# as14120_x31_adc.net
KiCad netlist of a schematic drawn in Altium Designer
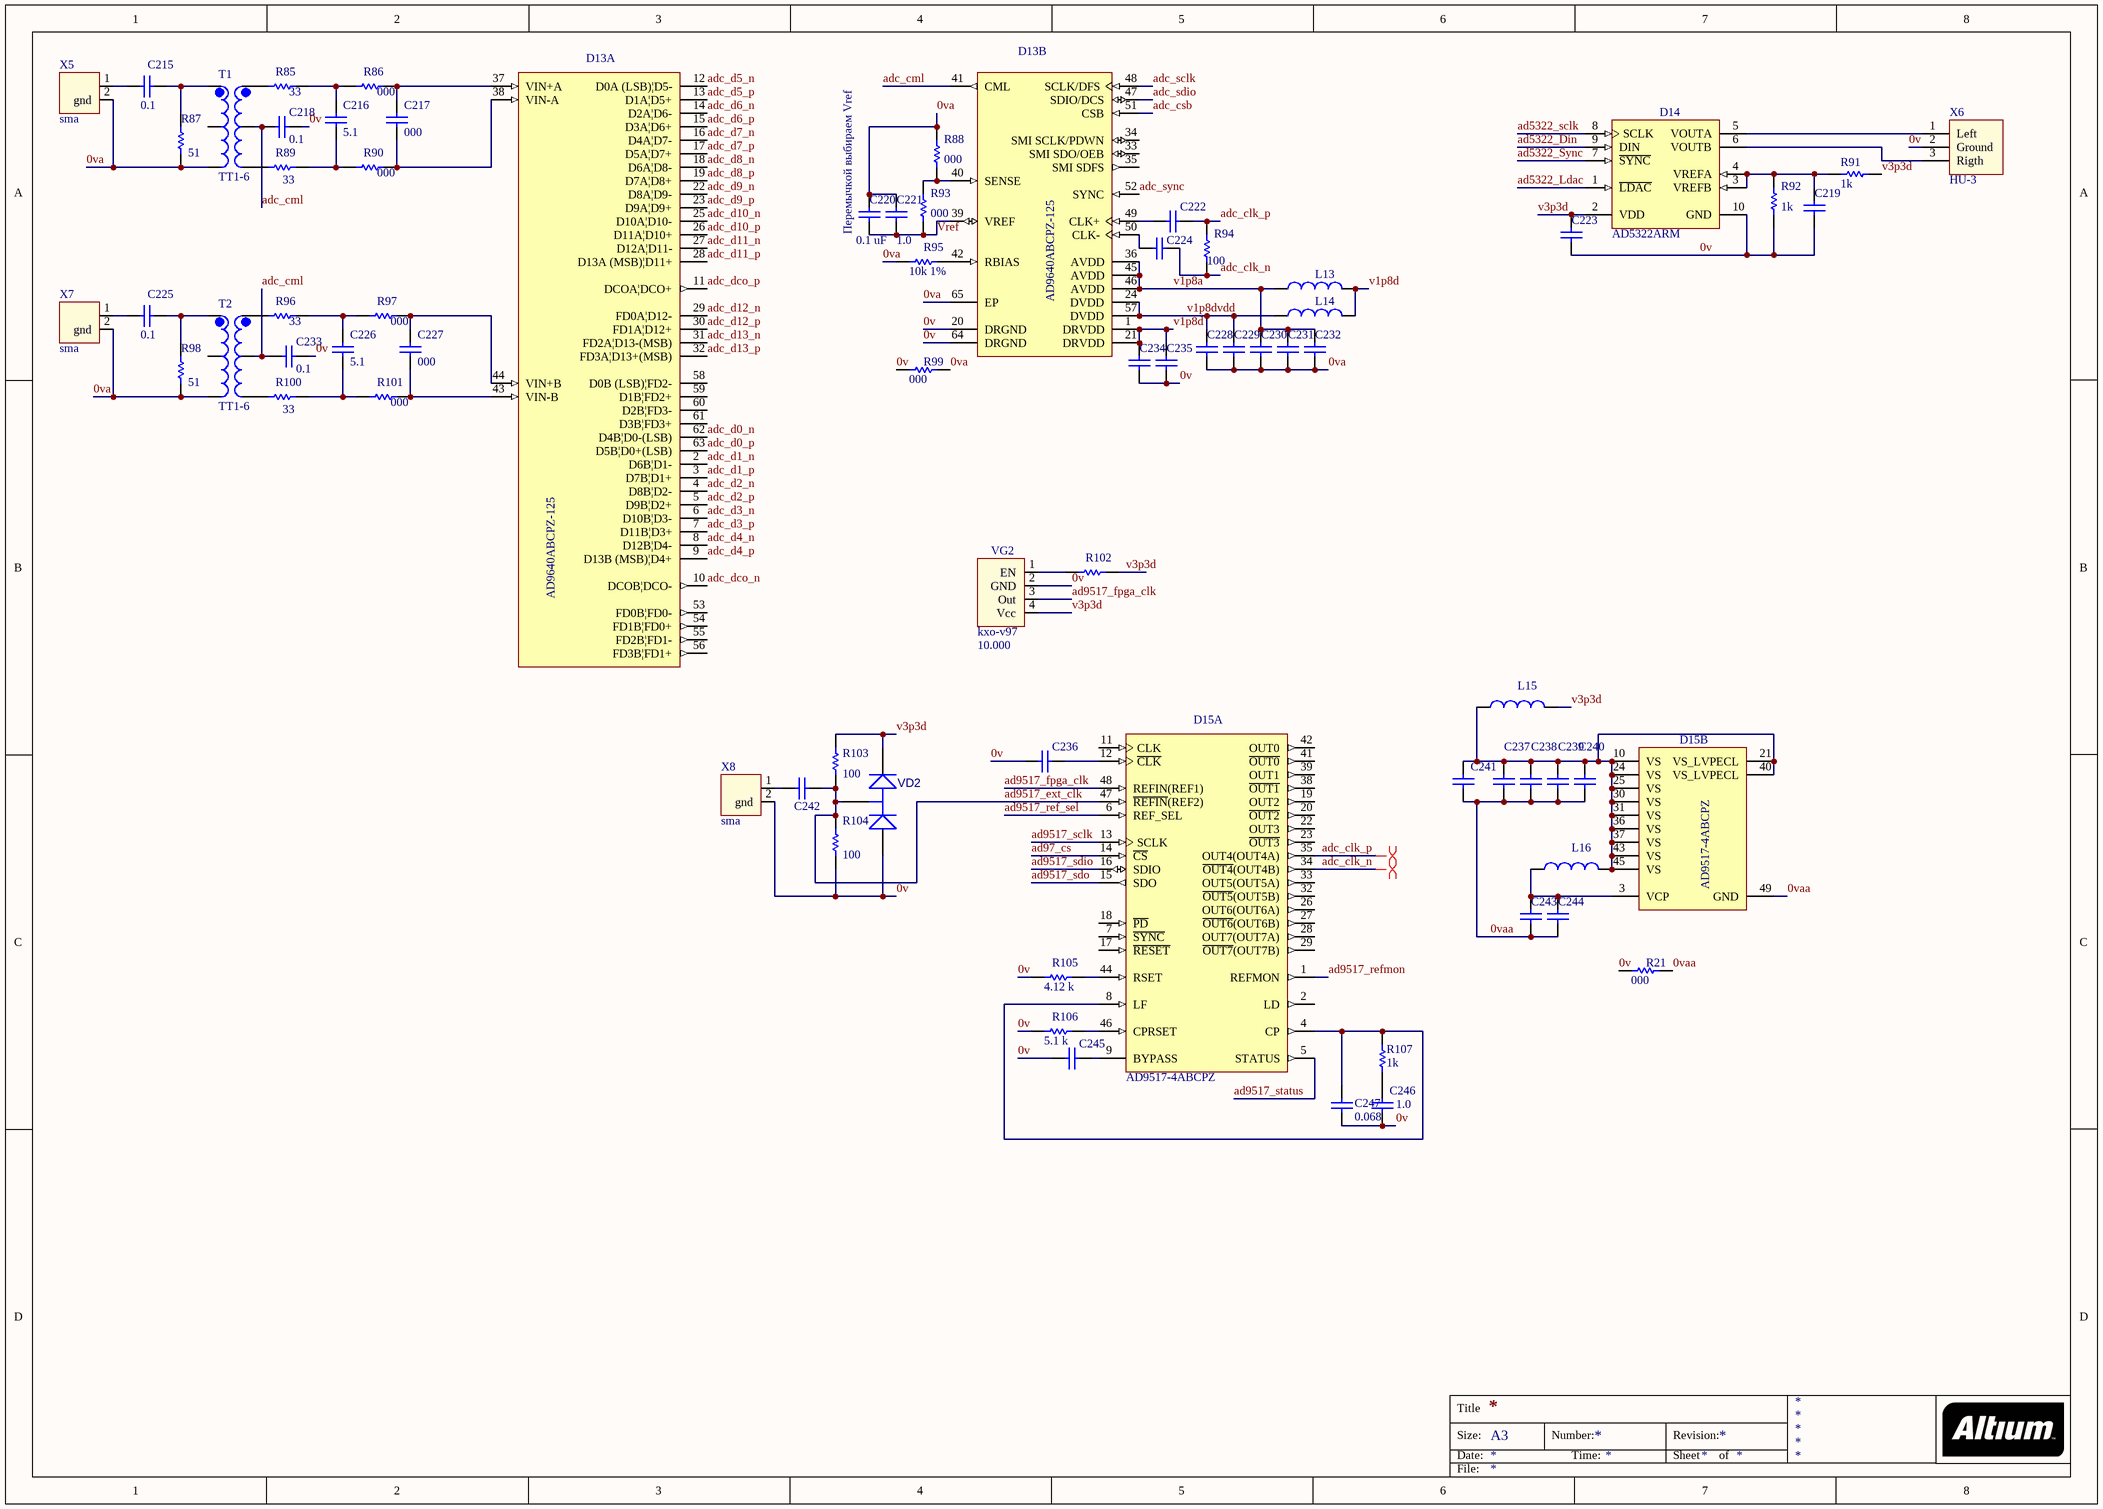
[diagram p0: as14120_x31_adc.SchDoc]

(export (version "E")
  (design (tool "Eeschema 10.0.6"))
  (components
    (comp (ref "C215")
      (value "0.1")
      (footprint "CAPC0402(1005)60_M")
      (description "CAP 1uF 10V ±20% 0402 (1005 Metric) Thickness 0.6mm SMD")
      (fields (field (name "TOLERANCE") "±20%") (field (name "Comment") "CAP 1uF 10V 0402(1005)"))
      (libsource (lib "as14120") (part "CAP_0402"))
    )
    (comp (ref "C216")
      (value "5.1")
      (footprint "CAPC0805(2012)100_N")
      (fields (field (name "Comment") "CAP_0805"))
      (libsource (lib "as14120") (part "CAP_0805"))
    )
    (comp (ref "C217")
      (value "000")
      (footprint "CAPC0805(2012)100_N")
      (fields (field (name "Comment") "CAP_0805"))
      (libsource (lib "as14120") (part "CAP_0805"))
    )
    (comp (ref "C218")
      (value "0.1")
      (footprint "CAPC0402(1005)60_M")
      (description "CAP 1uF 10V ±20% 0402 (1005 Metric) Thickness 0.6mm SMD")
      (fields (field (name "TOLERANCE") "±20%") (field (name "Comment") "CAP 1uF 10V 0402(1005)"))
      (libsource (lib "as14120") (part "CAP_0402"))
    )
    (comp (ref "C219")
      (value "CAP 1uF 10V 0402(1005)")
      (footprint "CAPC0402(1005)60_M")
      (description "CAP 1uF 10V ±20% 0402 (1005 Metric) Thickness 0.6mm SMD")
      (fields (field (name "TOLERANCE") "±20%"))
      (libsource (lib "as14120") (part "CAP_0402"))
    )
    (comp (ref "C220")
      (value "0.1 uF")
      (footprint "CAPC0402(1005)60_M")
      (description "CAP 1uF 10V ±20% 0402 (1005 Metric) Thickness 0.6mm SMD")
      (fields (field (name "TOLERANCE") "±20%") (field (name "Comment") "CAP 1uF 10V 0402(1005)"))
      (libsource (lib "as14120") (part "CAP_0402"))
    )
    (comp (ref "C221")
      (value "1.0")
      (footprint "CAPC0402(1005)60_M")
      (description "CAP 1uF 10V ±20% 0402 (1005 Metric) Thickness 0.6mm SMD")
      (fields (field (name "TOLERANCE") "±20%") (field (name "Comment") "CAP 1uF 10V 0402(1005)"))
      (libsource (lib "as14120") (part "CAP_0402"))
    )
    (comp (ref "C222")
      (value "CAP 1uF 10V 0402(1005)")
      (footprint "CAPC0402(1005)60_M")
      (description "CAP 1uF 10V ±20% 0402 (1005 Metric) Thickness 0.6mm SMD")
      (fields (field (name "TOLERANCE") "±20%"))
      (libsource (lib "as14120") (part "CAP_0402"))
    )
    (comp (ref "C223")
      (value "CAP 1uF 10V 0402(1005)")
      (footprint "CAPC0402(1005)60_M")
      (description "CAP 1uF 10V ±20% 0402 (1005 Metric) Thickness 0.6mm SMD")
      (fields (field (name "TOLERANCE") "±20%"))
      (libsource (lib "as14120") (part "CAP_0402"))
    )
    (comp (ref "C224")
      (value "CAP 1uF 10V 0402(1005)")
      (footprint "CAPC0402(1005)60_M")
      (description "CAP 1uF 10V ±20% 0402 (1005 Metric) Thickness 0.6mm SMD")
      (fields (field (name "TOLERANCE") "±20%"))
      (libsource (lib "as14120") (part "CAP_0402"))
    )
    (comp (ref "C225")
      (value "0.1")
      (footprint "CAPC0402(1005)60_M")
      (description "CAP 1uF 10V ±20% 0402 (1005 Metric) Thickness 0.6mm SMD")
      (fields (field (name "TOLERANCE") "±20%") (field (name "Comment") "CAP 1uF 10V 0402(1005)"))
      (libsource (lib "as14120") (part "CAP_0402"))
    )
    (comp (ref "C226")
      (value "5.1")
      (footprint "CAPC0805(2012)100_N")
      (fields (field (name "Comment") "CAP_0805"))
      (libsource (lib "as14120") (part "CAP_0805"))
    )
    (comp (ref "C227")
      (value "000")
      (footprint "CAPC0805(2012)100_N")
      (fields (field (name "Comment") "CAP_0805"))
      (libsource (lib "as14120") (part "CAP_0805"))
    )
    (comp (ref "C228")
      (value "CAP 1uF 10V 0402(1005)")
      (footprint "CAPC0402(1005)60_M")
      (description "CAP 1uF 10V ±20% 0402 (1005 Metric) Thickness 0.6mm SMD")
      (fields (field (name "TOLERANCE") "±20%"))
      (libsource (lib "as14120") (part "CAP_0402"))
    )
    (comp (ref "C229")
      (value "CAP 1uF 10V 0402(1005)")
      (footprint "CAPC0402(1005)60_M")
      (description "CAP 1uF 10V ±20% 0402 (1005 Metric) Thickness 0.6mm SMD")
      (fields (field (name "TOLERANCE") "±20%"))
      (libsource (lib "as14120") (part "CAP_0402"))
    )
    (comp (ref "C230")
      (value "CAP 1uF 10V 0402(1005)")
      (footprint "CAPC0402(1005)60_M")
      (description "CAP 1uF 10V ±20% 0402 (1005 Metric) Thickness 0.6mm SMD")
      (fields (field (name "TOLERANCE") "±20%"))
      (libsource (lib "as14120") (part "CAP_0402"))
    )
    (comp (ref "C231")
      (value "CAP 1uF 10V 0402(1005)")
      (footprint "CAPC0402(1005)60_M")
      (description "CAP 1uF 10V ±20% 0402 (1005 Metric) Thickness 0.6mm SMD")
      (fields (field (name "TOLERANCE") "±20%"))
      (libsource (lib "as14120") (part "CAP_0402"))
    )
    (comp (ref "C232")
      (value "CAP 1uF 10V 0402(1005)")
      (footprint "CAPC0402(1005)60_M")
      (description "CAP 1uF 10V ±20% 0402 (1005 Metric) Thickness 0.6mm SMD")
      (fields (field (name "TOLERANCE") "±20%"))
      (libsource (lib "as14120") (part "CAP_0402"))
    )
    (comp (ref "C233")
      (value "0.1")
      (footprint "CAPC0402(1005)60_M")
      (description "CAP 1uF 10V ±20% 0402 (1005 Metric) Thickness 0.6mm SMD")
      (fields (field (name "TOLERANCE") "±20%") (field (name "Comment") "CAP 1uF 10V 0402(1005)"))
      (libsource (lib "as14120") (part "CAP_0402"))
    )
    (comp (ref "C234")
      (value "CAP 1uF 10V 0402(1005)")
      (footprint "CAPC0402(1005)60_M")
      (description "CAP 1uF 10V ±20% 0402 (1005 Metric) Thickness 0.6mm SMD")
      (fields (field (name "TOLERANCE") "±20%"))
      (libsource (lib "as14120") (part "CAP_0402"))
    )
    (comp (ref "C235")
      (value "CAP 1uF 10V 0402(1005)")
      (footprint "CAPC0402(1005)60_M")
      (description "CAP 1uF 10V ±20% 0402 (1005 Metric) Thickness 0.6mm SMD")
      (fields (field (name "TOLERANCE") "±20%"))
      (libsource (lib "as14120") (part "CAP_0402"))
    )
    (comp (ref "C236")
      (value "CAP 1uF 10V 0402(1005)")
      (footprint "CAPC0402(1005)60_M")
      (description "CAP 1uF 10V ±20% 0402 (1005 Metric) Thickness 0.6mm SMD")
      (fields (field (name "TOLERANCE") "±20%"))
      (libsource (lib "as14120") (part "CAP_0402"))
    )
    (comp (ref "C237")
      (value "CAP 1uF 10V 0402(1005)")
      (footprint "CAPC0402(1005)60_M")
      (description "CAP 1uF 10V ±20% 0402 (1005 Metric) Thickness 0.6mm SMD")
      (fields (field (name "TOLERANCE") "±20%"))
      (libsource (lib "as14120") (part "CAP_0402"))
    )
    (comp (ref "C238")
      (value "CAP 1uF 10V 0402(1005)")
      (footprint "CAPC0402(1005)60_M")
      (description "CAP 1uF 10V ±20% 0402 (1005 Metric) Thickness 0.6mm SMD")
      (fields (field (name "TOLERANCE") "±20%"))
      (libsource (lib "as14120") (part "CAP_0402"))
    )
    (comp (ref "C239")
      (value "CAP 1uF 10V 0402(1005)")
      (footprint "CAPC0402(1005)60_M")
      (description "CAP 1uF 10V ±20% 0402 (1005 Metric) Thickness 0.6mm SMD")
      (fields (field (name "TOLERANCE") "±20%"))
      (libsource (lib "as14120") (part "CAP_0402"))
    )
    (comp (ref "C240")
      (value "CAP 1uF 10V 0402(1005)")
      (footprint "CAPC0402(1005)60_M")
      (description "CAP 1uF 10V ±20% 0402 (1005 Metric) Thickness 0.6mm SMD")
      (fields (field (name "TOLERANCE") "±20%"))
      (libsource (lib "as14120") (part "CAP_0402"))
    )
    (comp (ref "C241")
      (value "CAP 1uF 10V 0402(1005)")
      (footprint "CAPC0402(1005)60_M")
      (description "CAP 1uF 10V ±20% 0402 (1005 Metric) Thickness 0.6mm SMD")
      (fields (field (name "TOLERANCE") "±20%"))
      (libsource (lib "as14120") (part "CAP_0402"))
    )
    (comp (ref "C242")
      (value "CAP 1uF 10V 0402(1005)")
      (footprint "CAPC0402(1005)60_M")
      (description "CAP 1uF 10V ±20% 0402 (1005 Metric) Thickness 0.6mm SMD")
      (fields (field (name "TOLERANCE") "±20%"))
      (libsource (lib "as14120") (part "CAP_0402"))
    )
    (comp (ref "C243")
      (value "CAP 1uF 10V 0402(1005)")
      (footprint "CAPC0402(1005)60_M")
      (description "CAP 1uF 10V ±20% 0402 (1005 Metric) Thickness 0.6mm SMD")
      (fields (field (name "TOLERANCE") "±20%"))
      (libsource (lib "as14120") (part "CAP_0402"))
    )
    (comp (ref "C244")
      (value "CAP 1uF 10V 0402(1005)")
      (footprint "CAPC0402(1005)60_M")
      (description "CAP 1uF 10V ±20% 0402 (1005 Metric) Thickness 0.6mm SMD")
      (fields (field (name "TOLERANCE") "±20%"))
      (libsource (lib "as14120") (part "CAP_0402"))
    )
    (comp (ref "C245")
      (value "CAP 1uF 10V 0402(1005)")
      (footprint "CAPC0402(1005)60_M")
      (description "CAP 1uF 10V ±20% 0402 (1005 Metric) Thickness 0.6mm SMD")
      (fields (field (name "TOLERANCE") "±20%"))
      (libsource (lib "as14120") (part "CAP_0402"))
    )
    (comp (ref "C246")
      (value "1.0")
      (footprint "CAPC0805(2012)100_N")
      (fields (field (name "Comment") "CAP_0805"))
      (libsource (lib "as14120") (part "CAP_0805"))
    )
    (comp (ref "C247")
      (value "0.068")
      (footprint "CAPC0805(2012)100_N")
      (fields (field (name "Comment") "CAP_0805"))
      (libsource (lib "as14120") (part "CAP_0805"))
    )
    (comp (ref "D13")
      (value "AD9640ABCPZ-125")
      (footprint "CP-64-6_N")
      (fields (field (name "PART NUMBER") "AD9640-125") (field (name "MANUFACTURER") "Analog Devices"))
      (libsource (lib "Analog Devices Data Converters Analog-to-Digital Converters") (part "AD9640ABCPZ-125"))
    )
    (comp (ref "D14")
      (value "AD5322ARM")
      (footprint "RM-10_L")
      (fields (field (name "ADI PART NUMBER") "AD5322") (field (name "MANUFACTURER") "Analog Devices"))
      (libsource (lib "Analog Devices Data Converters Digital-to-Analog Converters") (part "AD5322ARM"))
    )
    (comp (ref "D15")
      (value "AD9517-4ABCPZ")
      (footprint "ADI-CP-48-8_L")
      (libsource (lib "Analog Devices RF IF Timing ICs and Clocks") (part "AD9517-4ABCPZ"))
    )
    (comp (ref "L13")
      (value "BLM21PG300SN1D")
      (footprint "CAPC0805(2012)100_N")
      (libsource (lib "as14120") (part "Ferrite_beat"))
    )
    (comp (ref "L14")
      (value "BLM21PG300SN1D")
      (footprint "CAPC0805(2012)100_N")
      (libsource (lib "as14120") (part "Ferrite_beat"))
    )
    (comp (ref "L15")
      (value "BLM21PG300SN1D")
      (footprint "CAPC0805(2012)100_N")
      (libsource (lib "as14120") (part "Ferrite_beat"))
    )
    (comp (ref "L16")
      (value "BLM21PG300SN1D")
      (footprint "CAPC0805(2012)100_N")
      (libsource (lib "as14120") (part "Ferrite_beat"))
    )
    (comp (ref "R21")
      (value "000")
      (footprint "RESC0603(1608)_L")
      (description "1K 0.1W 5% 0603 (1608 Metric)  SMD")
      (fields (field (name "TOLERANCE") "5 %") (field (name "POWER") "0.1 W"))
      (libsource (lib "as14120") (part "RES_0603"))
    )
    (comp (ref "R85")
      (value "33")
      (footprint "RESC0805(2012)_L")
      (description "1K 0.125W 1% 0805 (2012 Metric)  SMD")
      (fields (field (name "TOLERANCE") "1 %") (field (name "POWER") "0.125 W"))
      (libsource (lib "as14120") (part "RES_0805"))
    )
    (comp (ref "R86")
      (value "000")
      (footprint "RESC0805(2012)_L")
      (description "1K 0.125W 1% 0805 (2012 Metric)  SMD")
      (fields (field (name "TOLERANCE") "1 %") (field (name "POWER") "0.125 W"))
      (libsource (lib "as14120") (part "RES_0805"))
    )
    (comp (ref "R87")
      (value "51")
      (footprint "RESC0805(2012)_L")
      (description "1K 0.125W 1% 0805 (2012 Metric)  SMD")
      (fields (field (name "TOLERANCE") "1 %") (field (name "POWER") "0.125 W"))
      (libsource (lib "as14120") (part "RES_0805"))
    )
    (comp (ref "R88")
      (value "000")
      (footprint "RESC0603(1608)_L")
      (description "1K 0.1W 5% 0603 (1608 Metric)  SMD")
      (fields (field (name "TOLERANCE") "5 %") (field (name "POWER") "0.1 W"))
      (libsource (lib "as14120") (part "RES_0603"))
    )
    (comp (ref "R89")
      (value "33")
      (footprint "RESC0805(2012)_L")
      (description "1K 0.125W 1% 0805 (2012 Metric)  SMD")
      (fields (field (name "TOLERANCE") "1 %") (field (name "POWER") "0.125 W"))
      (libsource (lib "as14120") (part "RES_0805"))
    )
    (comp (ref "R90")
      (value "000")
      (footprint "RESC0805(2012)_L")
      (description "1K 0.125W 1% 0805 (2012 Metric)  SMD")
      (fields (field (name "TOLERANCE") "1 %") (field (name "POWER") "0.125 W"))
      (libsource (lib "as14120") (part "RES_0805"))
    )
    (comp (ref "R91")
      (value "1k")
      (footprint "RESC0603(1608)_L")
      (description "1K 0.1W 5% 0603 (1608 Metric)  SMD")
      (fields (field (name "TOLERANCE") "5 %") (field (name "POWER") "0.1 W"))
      (libsource (lib "as14120") (part "RES_0603"))
    )
    (comp (ref "R92")
      (value "1k")
      (footprint "RESC0603(1608)_L")
      (description "1K 0.1W 5% 0603 (1608 Metric)  SMD")
      (fields (field (name "TOLERANCE") "5 %") (field (name "POWER") "0.1 W"))
      (libsource (lib "as14120") (part "RES_0603"))
    )
    (comp (ref "R93")
      (value "000")
      (footprint "RESC0603(1608)_L")
      (description "1K 0.1W 5% 0603 (1608 Metric)  SMD")
      (fields (field (name "TOLERANCE") "5 %") (field (name "POWER") "0.1 W"))
      (libsource (lib "as14120") (part "RES_0603"))
    )
    (comp (ref "R94")
      (value "100")
      (footprint "RESC0805(2012)_L")
      (description "1K 0.125W 1% 0805 (2012 Metric)  SMD")
      (fields (field (name "TOLERANCE") "1 %") (field (name "POWER") "0.125 W"))
      (libsource (lib "as14120") (part "RES_0805"))
    )
    (comp (ref "R95")
      (value "10k 1%")
      (footprint "RESC0805(2012)_L")
      (description "1K 0.125W 1% 0805 (2012 Metric)  SMD")
      (fields (field (name "TOLERANCE") "1 %") (field (name "POWER") "0.125 W"))
      (libsource (lib "as14120") (part "RES_0805"))
    )
    (comp (ref "R96")
      (value "33")
      (footprint "RESC0805(2012)_L")
      (description "1K 0.125W 1% 0805 (2012 Metric)  SMD")
      (fields (field (name "TOLERANCE") "1 %") (field (name "POWER") "0.125 W"))
      (libsource (lib "as14120") (part "RES_0805"))
    )
    (comp (ref "R97")
      (value "000")
      (footprint "RESC0805(2012)_L")
      (description "1K 0.125W 1% 0805 (2012 Metric)  SMD")
      (fields (field (name "TOLERANCE") "1 %") (field (name "POWER") "0.125 W"))
      (libsource (lib "as14120") (part "RES_0805"))
    )
    (comp (ref "R98")
      (value "51")
      (footprint "RESC0805(2012)_L")
      (description "1K 0.125W 1% 0805 (2012 Metric)  SMD")
      (fields (field (name "TOLERANCE") "1 %") (field (name "POWER") "0.125 W"))
      (libsource (lib "as14120") (part "RES_0805"))
    )
    (comp (ref "R99")
      (value "000")
      (footprint "RESC0603(1608)_L")
      (description "1K 0.1W 5% 0603 (1608 Metric)  SMD")
      (fields (field (name "TOLERANCE") "5 %") (field (name "POWER") "0.1 W"))
      (libsource (lib "as14120") (part "RES_0603"))
    )
    (comp (ref "R100")
      (value "33")
      (footprint "RESC0805(2012)_L")
      (description "1K 0.125W 1% 0805 (2012 Metric)  SMD")
      (fields (field (name "TOLERANCE") "1 %") (field (name "POWER") "0.125 W"))
      (libsource (lib "as14120") (part "RES_0805"))
    )
    (comp (ref "R101")
      (value "000")
      (footprint "RESC0805(2012)_L")
      (description "1K 0.125W 1% 0805 (2012 Metric)  SMD")
      (fields (field (name "TOLERANCE") "1 %") (field (name "POWER") "0.125 W"))
      (libsource (lib "as14120") (part "RES_0805"))
    )
    (comp (ref "R102")
      (value "1K 5% 0603(1608)")
      (footprint "RESC0603(1608)_L")
      (description "1K 0.1W 5% 0603 (1608 Metric)  SMD")
      (fields (field (name "TOLERANCE") "5 %") (field (name "POWER") "0.1 W"))
      (libsource (lib "as14120") (part "RES_0603"))
    )
    (comp (ref "R103")
      (value "100")
      (footprint "RESC0805(2012)_L")
      (description "1K 0.125W 1% 0805 (2012 Metric)  SMD")
      (fields (field (name "TOLERANCE") "1 %") (field (name "POWER") "0.125 W"))
      (libsource (lib "as14120") (part "RES_0805"))
    )
    (comp (ref "R104")
      (value "100")
      (footprint "RESC0805(2012)_L")
      (description "1K 0.125W 1% 0805 (2012 Metric)  SMD")
      (fields (field (name "TOLERANCE") "1 %") (field (name "POWER") "0.125 W"))
      (libsource (lib "as14120") (part "RES_0805"))
    )
    (comp (ref "R105")
      (value "4.12 k")
      (footprint "RESC0805(2012)_L")
      (description "1K 0.125W 1% 0805 (2012 Metric)  SMD")
      (fields (field (name "TOLERANCE") "1 %") (field (name "POWER") "0.125 W"))
      (libsource (lib "as14120") (part "RES_0805"))
    )
    (comp (ref "R106")
      (value "5.1 k")
      (footprint "RESC0805(2012)_L")
      (description "1K 0.125W 1% 0805 (2012 Metric)  SMD")
      (fields (field (name "TOLERANCE") "1 %") (field (name "POWER") "0.125 W"))
      (libsource (lib "as14120") (part "RES_0805"))
    )
    (comp (ref "R107")
      (value "1k")
      (footprint "RESC0805(2012)_L")
      (description "1K 0.125W 1% 0805 (2012 Metric)  SMD")
      (fields (field (name "TOLERANCE") "1 %") (field (name "POWER") "0.125 W"))
      (libsource (lib "as14120") (part "RES_0805"))
    )
    (comp (ref "T1") (value "TT1-6") (footprint "TT!-6-KK81") (libsource (lib "as14120") (part "TT1-6-KK81")))
    (comp (ref "T2") (value "TT1-6") (footprint "TT!-6-KK81") (libsource (lib "as14120") (part "TT1-6-KK81")))
    (comp (ref "VD2")
      (value "BAV99")
      (footprint "SO-G3/X.9")
      (description "SOT23 Silicon Planar High-Speed Switching Series Diode Pair")
      (libsource (lib "alexsb") (part "BAV99"))
    )
    (comp (ref "VG2")
      (value "kxo-v97")
      (footprint "kxo-v97")
      (fields (field (name "ALTIUM_VALUE") "10.000"))
      (libsource (lib "as14120") (part "kxo-v97"))
    )
    (comp (ref "X5") (value "sma") (footprint "sma") (libsource (lib "as14120") (part "sma")))
    (comp (ref "X6") (value "HU-3") (footprint "HU-3") (libsource (lib "as14120") (part "HU-3")))
    (comp (ref "X7") (value "sma") (footprint "sma") (libsource (lib "as14120") (part "sma")))
    (comp (ref "X8") (value "sma") (footprint "sma") (libsource (lib "as14120") (part "sma")))
  )
  (nets
    (net (code "1") (name "/0v") (class "Default")
      (node (ref "C218") (pin "2") (pinfunction "2_2") (pintype "passive"))
      (node (ref "C219") (pin "1") (pinfunction "1_1") (pintype "passive"))
      (node (ref "C223") (pin "1") (pinfunction "1_1") (pintype "passive"))
      (node (ref "C233") (pin "2") (pinfunction "2_2") (pintype "passive"))
      (node (ref "C234") (pin "1") (pinfunction "1_1") (pintype "passive"))
      (node (ref "C235") (pin "1") (pinfunction "1_1") (pintype "passive"))
      (node (ref "C236") (pin "1") (pinfunction "1_1") (pintype "passive"))
      (node (ref "C245") (pin "1") (pinfunction "1_1") (pintype "passive"))
      (node (ref "C246") (pin "1") (pinfunction "1_1") (pintype "passive"))
      (node (ref "C247") (pin "1") (pinfunction "1_1") (pintype "passive"))
      (node (ref "D13") (pin "20") (pinfunction "DRGND_20") (pintype "power_in"))
      (node (ref "D13") (pin "64") (pinfunction "DRGND_64") (pintype "power_in"))
      (node (ref "D14") (pin "10") (pinfunction "GND_10") (pintype "power_in"))
      (node (ref "R104") (pin "1") (pinfunction "1_1") (pintype "passive"))
      (node (ref "R105") (pin "2") (pinfunction "2_2") (pintype "passive"))
      (node (ref "R106") (pin "2") (pinfunction "2_2") (pintype "passive"))
      (node (ref "R21") (pin "1") (pinfunction "1_1") (pintype "passive"))
      (node (ref "R92") (pin "2") (pinfunction "2_2") (pintype "passive"))
      (node (ref "R99") (pin "1") (pinfunction "1_1") (pintype "passive"))
      (node (ref "VD2") (pin "3") (pinfunction "A_3") (pintype "passive"))
      (node (ref "VG2") (pin "2") (pinfunction "GND_2") (pintype "passive"))
      (node (ref "X6") (pin "2") (pinfunction "Ground_2") (pintype "passive"))
      (node (ref "X8") (pin "2") (pinfunction "gnd_2") (pintype "passive"))
    )
    (net (code "2") (name "/0va") (class "Default")
      (node (ref "C220") (pin "2") (pinfunction "2_2") (pintype "passive"))
      (node (ref "C221") (pin "2") (pinfunction "2_2") (pintype "passive"))
      (node (ref "C228") (pin "1") (pinfunction "1_1") (pintype "passive"))
      (node (ref "C229") (pin "1") (pinfunction "1_1") (pintype "passive"))
      (node (ref "C230") (pin "1") (pinfunction "1_1") (pintype "passive"))
      (node (ref "C231") (pin "1") (pinfunction "1_1") (pintype "passive"))
      (node (ref "C232") (pin "1") (pinfunction "1_1") (pintype "passive"))
      (node (ref "D13") (pin "65") (pinfunction "EP_65") (pintype "power_in"))
      (node (ref "R87") (pin "1") (pinfunction "1_1") (pintype "passive"))
      (node (ref "R88") (pin "1") (pinfunction "1_1") (pintype "passive"))
      (node (ref "R95") (pin "2") (pinfunction "2_2") (pintype "passive"))
      (node (ref "R98") (pin "1") (pinfunction "1_1") (pintype "passive"))
      (node (ref "R99") (pin "2") (pinfunction "2_2") (pintype "passive"))
      (node (ref "T1") (pin "6") (pinfunction "6_6") (pintype "passive"))
      (node (ref "T2") (pin "6") (pinfunction "6_6") (pintype "passive"))
      (node (ref "X5") (pin "2") (pinfunction "gnd_2") (pintype "passive"))
      (node (ref "X7") (pin "2") (pinfunction "gnd_2") (pintype "passive"))
    )
    (net (code "3") (name "/0vaa") (class "Default")
      (node (ref "C237") (pin "1") (pinfunction "1_1") (pintype "passive"))
      (node (ref "C238") (pin "1") (pinfunction "1_1") (pintype "passive"))
      (node (ref "C239") (pin "1") (pinfunction "1_1") (pintype "passive"))
      (node (ref "C240") (pin "1") (pinfunction "1_1") (pintype "passive"))
      (node (ref "C241") (pin "1") (pinfunction "1_1") (pintype "passive"))
      (node (ref "C243") (pin "1") (pinfunction "1_1") (pintype "passive"))
      (node (ref "C244") (pin "1") (pinfunction "1_1") (pintype "passive"))
      (node (ref "D15") (pin "49") (pinfunction "GND_49") (pintype "power_in"))
      (node (ref "R21") (pin "2") (pinfunction "2_2") (pintype "passive"))
    )
    (net (code "4") (name "/Vref") (class "Default")
      (node (ref "C220") (pin "1") (pinfunction "1_1") (pintype "passive"))
      (node (ref "C221") (pin "1") (pinfunction "1_1") (pintype "passive"))
      (node (ref "D13") (pin "39") (pinfunction "VREF_39") (pintype "bidirectional"))
      (node (ref "R93") (pin "2") (pinfunction "2_2") (pintype "passive"))
    )
    (net (code "5") (name "/ad97_cs") (class "Default")
      (node (ref "D15") (pin "14") (pinfunction "~{CS}_14") (pintype "input"))
    )
    (net (code "6") (name "/ad5322_Din") (class "Default")
      (node (ref "D14") (pin "9") (pinfunction "DIN_9") (pintype "input"))
    )
    (net (code "7") (name "/ad5322_Ldac") (class "Default")
      (node (ref "D14") (pin "1") (pinfunction "~{LDAC}_1") (pintype "input"))
    )
    (net (code "8") (name "/ad5322_Sync") (class "Default")
      (node (ref "D14") (pin "7") (pinfunction "~{SYNC}_7") (pintype "input"))
    )
    (net (code "9") (name "/ad5322_sclk") (class "Default")
      (node (ref "D14") (pin "8") (pinfunction "SCLK_8") (pintype "input"))
    )
    (net (code "10") (name "/ad9517_ext_clk") (class "Default")
      (node (ref "C242") (pin "2") (pinfunction "2_2") (pintype "passive"))
      (node (ref "D15") (pin "47") (pinfunction "~{REFIN}(REF2)_47") (pintype "input"))
      (node (ref "R103") (pin "1") (pinfunction "1_1") (pintype "passive"))
      (node (ref "R104") (pin "2") (pinfunction "2_2") (pintype "passive"))
      (node (ref "VD2") (pin "1") (pinfunction "C_1") (pintype "passive"))
    )
    (net (code "11") (name "/ad9517_fpga_clk") (class "Default")
      (node (ref "D15") (pin "48") (pinfunction "REFIN(REF1)_48") (pintype "input"))
      (node (ref "VG2") (pin "3") (pinfunction "Out_3") (pintype "passive"))
    )
    (net (code "12") (name "/ad9517_ref_sel") (class "Default")
      (node (ref "D15") (pin "6") (pinfunction "REF_SEL_6") (pintype "input"))
    )
    (net (code "13") (name "/ad9517_refmon") (class "Default")
      (node (ref "D15") (pin "1") (pinfunction "REFMON_1") (pintype "output"))
    )
    (net (code "14") (name "/ad9517_sclk") (class "Default")
      (node (ref "D15") (pin "13") (pinfunction "SCLK_13") (pintype "input"))
    )
    (net (code "15") (name "/ad9517_sdio") (class "Default")
      (node (ref "D15") (pin "16") (pinfunction "SDIO_16") (pintype "bidirectional"))
    )
    (net (code "16") (name "/ad9517_sdo") (class "Default")
      (node (ref "D15") (pin "15") (pinfunction "SDO_15") (pintype "output"))
    )
    (net (code "17") (name "/ad9517_status") (class "Default")
      (node (ref "D15") (pin "5") (pinfunction "STATUS_5") (pintype "output"))
    )
    (net (code "18") (name "/adc_clk_n") (class "Default")
      (node (ref "C224") (pin "1") (pinfunction "1_1") (pintype "passive"))
      (node (ref "D15") (pin "34") (pinfunction "~{OUT4}(OUT4B)_34") (pintype "output"))
      (node (ref "R94") (pin "1") (pinfunction "1_1") (pintype "passive"))
    )
    (net (code "19") (name "/adc_clk_p") (class "Default")
      (node (ref "C222") (pin "1") (pinfunction "1_1") (pintype "passive"))
      (node (ref "D15") (pin "35") (pinfunction "OUT4(OUT4A)_35") (pintype "output"))
      (node (ref "R94") (pin "2") (pinfunction "2_2") (pintype "passive"))
    )
    (net (code "20") (name "/adc_cml") (class "Default")
      (node (ref "C218") (pin "1") (pinfunction "1_1") (pintype "passive"))
      (node (ref "C233") (pin "1") (pinfunction "1_1") (pintype "passive"))
      (node (ref "D13") (pin "41") (pinfunction "CML_41") (pintype "output"))
      (node (ref "T1") (pin "2") (pinfunction "2_2") (pintype "passive"))
      (node (ref "T2") (pin "2") (pinfunction "2_2") (pintype "passive"))
    )
    (net (code "21") (name "/adc_csb") (class "Default")
      (node (ref "D13") (pin "51") (pinfunction "CSB_51") (pintype "input"))
    )
    (net (code "22") (name "/adc_d0_n") (class "Default")
      (node (ref "D13") (pin "62") (pinfunction "D4B¦D0-(LSB)_62") (pintype "tri_state"))
    )
    (net (code "23") (name "/adc_d0_p") (class "Default")
      (node (ref "D13") (pin "63") (pinfunction "D5B¦D0+(LSB)_63") (pintype "tri_state"))
    )
    (net (code "24") (name "/adc_d1_n") (class "Default")
      (node (ref "D13") (pin "2") (pinfunction "D6B¦D1-_2") (pintype "tri_state"))
    )
    (net (code "25") (name "/adc_d1_p") (class "Default")
      (node (ref "D13") (pin "3") (pinfunction "D7B¦D1+_3") (pintype "tri_state"))
    )
    (net (code "26") (name "/adc_d2_n") (class "Default")
      (node (ref "D13") (pin "4") (pinfunction "D8B¦D2-_4") (pintype "tri_state"))
    )
    (net (code "27") (name "/adc_d2_p") (class "Default")
      (node (ref "D13") (pin "5") (pinfunction "D9B¦D2+_5") (pintype "tri_state"))
    )
    (net (code "28") (name "/adc_d3_n") (class "Default")
      (node (ref "D13") (pin "6") (pinfunction "D10B¦D3-_6") (pintype "tri_state"))
    )
    (net (code "29") (name "/adc_d3_p") (class "Default")
      (node (ref "D13") (pin "7") (pinfunction "D11B¦D3+_7") (pintype "tri_state"))
    )
    (net (code "30") (name "/adc_d4_n") (class "Default")
      (node (ref "D13") (pin "8") (pinfunction "D12B¦D4-_8") (pintype "tri_state"))
    )
    (net (code "31") (name "/adc_d4_p") (class "Default")
      (node (ref "D13") (pin "9") (pinfunction "D13B_(MSB)¦D4+_9") (pintype "tri_state"))
    )
    (net (code "32") (name "/adc_d5_n") (class "Default")
      (node (ref "D13") (pin "12") (pinfunction "D0A_(LSB)¦D5-_12") (pintype "tri_state"))
    )
    (net (code "33") (name "/adc_d5_p") (class "Default")
      (node (ref "D13") (pin "13") (pinfunction "D1A¦D5+_13") (pintype "tri_state"))
    )
    (net (code "34") (name "/adc_d6_n") (class "Default")
      (node (ref "D13") (pin "14") (pinfunction "D2A¦D6-_14") (pintype "tri_state"))
    )
    (net (code "35") (name "/adc_d6_p") (class "Default")
      (node (ref "D13") (pin "15") (pinfunction "D3A¦D6+_15") (pintype "tri_state"))
    )
    (net (code "36") (name "/adc_d7_n") (class "Default")
      (node (ref "D13") (pin "16") (pinfunction "D4A¦D7-_16") (pintype "tri_state"))
    )
    (net (code "37") (name "/adc_d7_p") (class "Default")
      (node (ref "D13") (pin "17") (pinfunction "D5A¦D7+_17") (pintype "tri_state"))
    )
    (net (code "38") (name "/adc_d8_n") (class "Default")
      (node (ref "D13") (pin "18") (pinfunction "D6A¦D8-_18") (pintype "tri_state"))
    )
    (net (code "39") (name "/adc_d8_p") (class "Default")
      (node (ref "D13") (pin "19") (pinfunction "D7A¦D8+_19") (pintype "tri_state"))
    )
    (net (code "40") (name "/adc_d9_n") (class "Default")
      (node (ref "D13") (pin "22") (pinfunction "D8A¦D9-_22") (pintype "tri_state"))
    )
    (net (code "41") (name "/adc_d9_p") (class "Default")
      (node (ref "D13") (pin "23") (pinfunction "D9A¦D9+_23") (pintype "tri_state"))
    )
    (net (code "42") (name "/adc_d10_n") (class "Default")
      (node (ref "D13") (pin "25") (pinfunction "D10A¦D10-_25") (pintype "tri_state"))
    )
    (net (code "43") (name "/adc_d10_p") (class "Default")
      (node (ref "D13") (pin "26") (pinfunction "D11A¦D10+_26") (pintype "tri_state"))
    )
    (net (code "44") (name "/adc_d11_n") (class "Default")
      (node (ref "D13") (pin "27") (pinfunction "D12A¦D11-_27") (pintype "tri_state"))
    )
    (net (code "45") (name "/adc_d11_p") (class "Default")
      (node (ref "D13") (pin "28") (pinfunction "D13A_(MSB)¦D11+_28") (pintype "tri_state"))
    )
    (net (code "46") (name "/adc_d12_n") (class "Default")
      (node (ref "D13") (pin "29") (pinfunction "FD0A¦D12-_29") (pintype "tri_state"))
    )
    (net (code "47") (name "/adc_d12_p") (class "Default")
      (node (ref "D13") (pin "30") (pinfunction "FD1A¦D12+_30") (pintype "tri_state"))
    )
    (net (code "48") (name "/adc_d13_n") (class "Default")
      (node (ref "D13") (pin "31") (pinfunction "FD2A¦D13-(MSB)_31") (pintype "tri_state"))
    )
    (net (code "49") (name "/adc_d13_p") (class "Default")
      (node (ref "D13") (pin "32") (pinfunction "FD3A¦D13+(MSB)_32") (pintype "tri_state"))
    )
    (net (code "50") (name "/adc_dco_n") (class "Default")
      (node (ref "D13") (pin "10") (pinfunction "DCOB¦DCO-_10") (pintype "output"))
    )
    (net (code "51") (name "/adc_dco_p") (class "Default")
      (node (ref "D13") (pin "11") (pinfunction "DCOA¦DCO+_11") (pintype "output"))
    )
    (net (code "52") (name "/adc_sclk") (class "Default")
      (node (ref "D13") (pin "48") (pinfunction "SCLK/DFS_48") (pintype "input"))
    )
    (net (code "53") (name "/adc_sdio") (class "Default")
      (node (ref "D13") (pin "47") (pinfunction "SDIO/DCS_47") (pintype "bidirectional"))
    )
    (net (code "54") (name "/adc_sync") (class "Default")
      (node (ref "D13") (pin "52") (pinfunction "SYNC_52") (pintype "input"))
    )
    (net (code "55") (name "/v1p8a") (class "Default")
      (node (ref "C230") (pin "2") (pinfunction "2_2") (pintype "passive"))
      (node (ref "C231") (pin "2") (pinfunction "2_2") (pintype "passive"))
      (node (ref "C232") (pin "2") (pinfunction "2_2") (pintype "passive"))
      (node (ref "D13") (pin "36") (pinfunction "AVDD_36") (pintype "power_in"))
      (node (ref "D13") (pin "45") (pinfunction "AVDD_45") (pintype "power_in"))
      (node (ref "D13") (pin "46") (pinfunction "AVDD_46") (pintype "power_in"))
      (node (ref "L13") (pin "1") (pinfunction "1_1") (pintype "passive"))
    )
    (net (code "56") (name "/v1p8d") (class "Default")
      (node (ref "C234") (pin "2") (pinfunction "2_2") (pintype "passive"))
      (node (ref "C235") (pin "2") (pinfunction "2_2") (pintype "passive"))
      (node (ref "D13") (pin "1") (pinfunction "DRVDD_1") (pintype "power_in"))
      (node (ref "D13") (pin "21") (pinfunction "DRVDD_21") (pintype "power_in"))
      (node (ref "L13") (pin "2") (pinfunction "2_2") (pintype "passive"))
      (node (ref "L14") (pin "2") (pinfunction "2_2") (pintype "passive"))
    )
    (net (code "57") (name "/v1p8dvdd") (class "Default")
      (node (ref "C228") (pin "2") (pinfunction "2_2") (pintype "passive"))
      (node (ref "C229") (pin "2") (pinfunction "2_2") (pintype "passive"))
      (node (ref "D13") (pin "24") (pinfunction "DVDD_24") (pintype "power_in"))
      (node (ref "D13") (pin "57") (pinfunction "DVDD_57") (pintype "power_in"))
      (node (ref "L14") (pin "1") (pinfunction "1_1") (pintype "passive"))
    )
    (net (code "58") (name "/v3p3d") (class "Default")
      (node (ref "C223") (pin "2") (pinfunction "2_2") (pintype "passive"))
      (node (ref "D14") (pin "2") (pinfunction "VDD_2") (pintype "power_in"))
      (node (ref "L15") (pin "2") (pinfunction "2_2") (pintype "passive"))
      (node (ref "R102") (pin "1") (pinfunction "1_1") (pintype "passive"))
      (node (ref "R103") (pin "2") (pinfunction "2_2") (pintype "passive"))
      (node (ref "R91") (pin "2") (pinfunction "2_2") (pintype "passive"))
      (node (ref "VD2") (pin "2") (pinfunction "K_2") (pintype "passive"))
      (node (ref "VG2") (pin "4") (pinfunction "Vcc_4") (pintype "passive"))
    )
    (net (code "59") (name "Net-(C215-Pad1)") (class "Default")
      (node (ref "C215") (pin "1") (pinfunction "1_1") (pintype "passive"))
      (node (ref "X5") (pin "1") (pintype "passive"))
    )
    (net (code "60") (name "Net-(C215-Pad2)") (class "Default")
      (node (ref "C215") (pin "2") (pinfunction "2_2") (pintype "passive"))
      (node (ref "R87") (pin "2") (pinfunction "2_2") (pintype "passive"))
      (node (ref "T1") (pin "4") (pinfunction "4_4") (pintype "passive"))
    )
    (net (code "61") (name "Net-(C216-Pad1)") (class "Default")
      (node (ref "C216") (pin "1") (pinfunction "1_1") (pintype "passive"))
      (node (ref "R89") (pin "1") (pinfunction "1_1") (pintype "passive"))
      (node (ref "R90") (pin "2") (pinfunction "2_2") (pintype "passive"))
    )
    (net (code "62") (name "Net-(C216-Pad2)") (class "Default")
      (node (ref "C216") (pin "2") (pinfunction "2_2") (pintype "passive"))
      (node (ref "R85") (pin "1") (pinfunction "1_1") (pintype "passive"))
      (node (ref "R86") (pin "2") (pinfunction "2_2") (pintype "passive"))
    )
    (net (code "63") (name "Net-(C225-Pad1)") (class "Default")
      (node (ref "C225") (pin "1") (pinfunction "1_1") (pintype "passive"))
      (node (ref "X7") (pin "1") (pintype "passive"))
    )
    (net (code "64") (name "Net-(C225-Pad2)") (class "Default")
      (node (ref "C225") (pin "2") (pinfunction "2_2") (pintype "passive"))
      (node (ref "R98") (pin "2") (pinfunction "2_2") (pintype "passive"))
      (node (ref "T2") (pin "4") (pinfunction "4_4") (pintype "passive"))
    )
    (net (code "65") (name "Net-(C226-Pad1)") (class "Default")
      (node (ref "C226") (pin "1") (pinfunction "1_1") (pintype "passive"))
      (node (ref "R100") (pin "1") (pinfunction "1_1") (pintype "passive"))
      (node (ref "R101") (pin "2") (pinfunction "2_2") (pintype "passive"))
    )
    (net (code "66") (name "Net-(C226-Pad2)") (class "Default")
      (node (ref "C226") (pin "2") (pinfunction "2_2") (pintype "passive"))
      (node (ref "R96") (pin "1") (pinfunction "1_1") (pintype "passive"))
      (node (ref "R97") (pin "2") (pinfunction "2_2") (pintype "passive"))
    )
    (net (code "67") (name "Net-(C237-Pad2)") (class "Default")
      (node (ref "C237") (pin "2") (pinfunction "2_2") (pintype "passive"))
      (node (ref "C238") (pin "2") (pinfunction "2_2") (pintype "passive"))
      (node (ref "C239") (pin "2") (pinfunction "2_2") (pintype "passive"))
      (node (ref "C240") (pin "2") (pinfunction "2_2") (pintype "passive"))
      (node (ref "C241") (pin "2") (pinfunction "2_2") (pintype "passive"))
      (node (ref "D15") (pin "10") (pinfunction "VS_10") (pintype "power_in"))
      (node (ref "D15") (pin "21") (pinfunction "VS_LVPECL_21") (pintype "power_in"))
      (node (ref "D15") (pin "24") (pinfunction "VS_24") (pintype "power_in"))
      (node (ref "D15") (pin "25") (pinfunction "VS_25") (pintype "power_in"))
      (node (ref "D15") (pin "30") (pinfunction "VS_30") (pintype "power_in"))
      (node (ref "D15") (pin "31") (pinfunction "VS_31") (pintype "power_in"))
      (node (ref "D15") (pin "36") (pinfunction "VS_36") (pintype "power_in"))
      (node (ref "D15") (pin "37") (pinfunction "VS_37") (pintype "power_in"))
      (node (ref "D15") (pin "40") (pinfunction "VS_LVPECL_40") (pintype "power_in"))
      (node (ref "D15") (pin "43") (pinfunction "VS_43") (pintype "power_in"))
      (node (ref "D15") (pin "45") (pinfunction "VS_45") (pintype "power_in"))
      (node (ref "L15") (pin "1") (pinfunction "1_1") (pintype "passive"))
      (node (ref "L16") (pin "2") (pinfunction "2_2") (pintype "passive"))
    )
    (net (code "68") (name "Net-(C242-Pad1)") (class "Default")
      (node (ref "C242") (pin "1") (pinfunction "1_1") (pintype "passive"))
      (node (ref "X8") (pin "1") (pintype "passive"))
    )
    (net (code "69") (name "Net-(C246-Pad2)") (class "Default")
      (node (ref "C246") (pin "2") (pinfunction "2_2") (pintype "passive"))
      (node (ref "R107") (pin "2") (pinfunction "2_2") (pintype "passive"))
    )
    (net (code "70") (name "Net-(D13A-VIN+A)") (class "Default")
      (node (ref "C217") (pin "2") (pinfunction "2_2") (pintype "passive"))
      (node (ref "D13") (pin "37") (pinfunction "VIN+A_37") (pintype "input"))
      (node (ref "R86") (pin "1") (pinfunction "1_1") (pintype "passive"))
    )
    (net (code "71") (name "Net-(D13A-VIN+B)") (class "Default")
      (node (ref "C227") (pin "2") (pinfunction "2_2") (pintype "passive"))
      (node (ref "D13") (pin "44") (pinfunction "VIN+B_44") (pintype "input"))
      (node (ref "R97") (pin "1") (pinfunction "1_1") (pintype "passive"))
    )
    (net (code "72") (name "Net-(D13A-VIN-A)") (class "Default")
      (node (ref "C217") (pin "1") (pinfunction "1_1") (pintype "passive"))
      (node (ref "D13") (pin "38") (pinfunction "VIN-A_38") (pintype "input"))
      (node (ref "R90") (pin "1") (pinfunction "1_1") (pintype "passive"))
    )
    (net (code "73") (name "Net-(D13A-VIN-B)") (class "Default")
      (node (ref "C227") (pin "1") (pinfunction "1_1") (pintype "passive"))
      (node (ref "D13") (pin "43") (pinfunction "VIN-B_43") (pintype "input"))
      (node (ref "R101") (pin "1") (pinfunction "1_1") (pintype "passive"))
    )
    (net (code "74") (name "Net-(D13B-CLK+)") (class "Default")
      (node (ref "C222") (pin "2") (pinfunction "2_2") (pintype "passive"))
      (node (ref "D13") (pin "49") (pinfunction "CLK+_49") (pintype "input"))
    )
    (net (code "75") (name "Net-(D13B-CLK-)") (class "Default")
      (node (ref "C224") (pin "2") (pinfunction "2_2") (pintype "passive"))
      (node (ref "D13") (pin "50") (pinfunction "CLK-_50") (pintype "input"))
    )
    (net (code "76") (name "Net-(D13B-RBIAS)") (class "Default")
      (node (ref "D13") (pin "42") (pinfunction "RBIAS_42") (pintype "input"))
      (node (ref "R95") (pin "1") (pinfunction "1_1") (pintype "passive"))
    )
    (net (code "77") (name "Net-(D13B-SENSE)") (class "Default")
      (node (ref "D13") (pin "40") (pinfunction "SENSE_40") (pintype "input"))
      (node (ref "R88") (pin "2") (pinfunction "2_2") (pintype "passive"))
      (node (ref "R93") (pin "1") (pinfunction "1_1") (pintype "passive"))
    )
    (net (code "78") (name "Net-(D14-VOUTA)") (class "Default")
      (node (ref "D14") (pin "5") (pinfunction "VOUTA_5") (pintype "tri_state"))
      (node (ref "X6") (pin "1") (pinfunction "Left_1") (pintype "passive"))
    )
    (net (code "79") (name "Net-(D14-VOUTB)") (class "Default")
      (node (ref "D14") (pin "6") (pinfunction "VOUTB_6") (pintype "tri_state"))
      (node (ref "X6") (pin "3") (pinfunction "Rigth_3") (pintype "passive"))
    )
    (net (code "80") (name "Net-(D14-VREFA)") (class "Default")
      (node (ref "C219") (pin "2") (pinfunction "2_2") (pintype "passive"))
      (node (ref "D14") (pin "3") (pinfunction "VREFB_3") (pintype "input"))
      (node (ref "D14") (pin "4") (pinfunction "VREFA_4") (pintype "input"))
      (node (ref "R91") (pin "1") (pinfunction "1_1") (pintype "passive"))
      (node (ref "R92") (pin "1") (pinfunction "1_1") (pintype "passive"))
    )
    (net (code "81") (name "Net-(D15A-BYPASS)") (class "Default")
      (node (ref "C245") (pin "2") (pinfunction "2_2") (pintype "passive"))
      (node (ref "D15") (pin "9") (pinfunction "BYPASS_9") (pintype "passive"))
    )
    (net (code "82") (name "Net-(D15A-CP)") (class "Default")
      (node (ref "C247") (pin "2") (pinfunction "2_2") (pintype "passive"))
      (node (ref "D15") (pin "4") (pinfunction "CP_4") (pintype "output"))
      (node (ref "D15") (pin "8") (pinfunction "LF_8") (pintype "input"))
      (node (ref "R107") (pin "1") (pinfunction "1_1") (pintype "passive"))
    )
    (net (code "83") (name "Net-(D15A-CPRSET)") (class "Default")
      (node (ref "D15") (pin "46") (pinfunction "CPRSET_46") (pintype "input"))
      (node (ref "R106") (pin "1") (pinfunction "1_1") (pintype "passive"))
    )
    (net (code "84") (name "Net-(D15A-RSET)") (class "Default")
      (node (ref "D15") (pin "44") (pinfunction "RSET_44") (pintype "input"))
      (node (ref "R105") (pin "1") (pinfunction "1_1") (pintype "passive"))
    )
    (net (code "85") (name "Net-(D15A-~{CLK})") (class "Default")
      (node (ref "C236") (pin "2") (pinfunction "2_2") (pintype "passive"))
      (node (ref "D15") (pin "12") (pinfunction "~{CLK}_12") (pintype "input"))
    )
    (net (code "86") (name "Net-(D15B-VCP)") (class "Default")
      (node (ref "C243") (pin "2") (pinfunction "2_2") (pintype "passive"))
      (node (ref "C244") (pin "2") (pinfunction "2_2") (pintype "passive"))
      (node (ref "D15") (pin "3") (pinfunction "VCP_3") (pintype "power_in"))
      (node (ref "L16") (pin "1") (pinfunction "1_1") (pintype "passive"))
    )
    (net (code "87") (name "Net-(R85-Pad2)") (class "Default")
      (node (ref "R85") (pin "2") (pinfunction "2_2") (pintype "passive"))
      (node (ref "T1") (pin "3") (pinfunction "3_3") (pintype "passive"))
    )
    (net (code "88") (name "Net-(R89-Pad2)") (class "Default")
      (node (ref "R89") (pin "2") (pinfunction "2_2") (pintype "passive"))
      (node (ref "T1") (pin "1") (pinfunction "1_1") (pintype "passive"))
    )
    (net (code "89") (name "Net-(R96-Pad2)") (class "Default")
      (node (ref "R96") (pin "2") (pinfunction "2_2") (pintype "passive"))
      (node (ref "T2") (pin "3") (pinfunction "3_3") (pintype "passive"))
    )
    (net (code "90") (name "Net-(R100-Pad2)") (class "Default")
      (node (ref "R100") (pin "2") (pinfunction "2_2") (pintype "passive"))
      (node (ref "T2") (pin "1") (pinfunction "1_1") (pintype "passive"))
    )
    (net (code "91") (name "Net-(VG2-EN)") (class "Default")
      (node (ref "R102") (pin "2") (pinfunction "2_2") (pintype "passive"))
      (node (ref "VG2") (pin "1") (pinfunction "EN_1") (pintype "passive"))
    )
    (net (code "92") (name "unconnected-(D13A-D0B_(LSB)¦FD2--Pad58)") (class "Default")
      (node (ref "D13") (pin "58") (pinfunction "D0B_(LSB)¦FD2-_58") (pintype "tri_state"))
    )
    (net (code "93") (name "unconnected-(D13A-D1B¦FD2+-Pad59)") (class "Default")
      (node (ref "D13") (pin "59") (pinfunction "D1B¦FD2+_59") (pintype "tri_state"))
    )
    (net (code "94") (name "unconnected-(D13A-D2B¦FD3--Pad60)") (class "Default")
      (node (ref "D13") (pin "60") (pinfunction "D2B¦FD3-_60") (pintype "tri_state"))
    )
    (net (code "95") (name "unconnected-(D13A-D3B¦FD3+-Pad61)") (class "Default")
      (node (ref "D13") (pin "61") (pinfunction "D3B¦FD3+_61") (pintype "tri_state"))
    )
    (net (code "96") (name "unconnected-(D13A-FD0B¦FD0--Pad53)") (class "Default")
      (node (ref "D13") (pin "53") (pinfunction "FD0B¦FD0-_53") (pintype "output"))
    )
    (net (code "97") (name "unconnected-(D13A-FD1B¦FD0+-Pad54)") (class "Default")
      (node (ref "D13") (pin "54") (pinfunction "FD1B¦FD0+_54") (pintype "output"))
    )
    (net (code "98") (name "unconnected-(D13A-FD2B¦FD1--Pad55)") (class "Default")
      (node (ref "D13") (pin "55") (pinfunction "FD2B¦FD1-_55") (pintype "output"))
    )
    (net (code "99") (name "unconnected-(D13A-FD3B¦FD1+-Pad56)") (class "Default")
      (node (ref "D13") (pin "56") (pinfunction "FD3B¦FD1+_56") (pintype "output"))
    )
    (net (code "100") (name "unconnected-(D13B-SMI_SCLK{slash}PDWN-Pad34)") (class "Default")
      (node (ref "D13") (pin "34") (pinfunction "SMI_SCLK/PDWN_34") (pintype "bidirectional"))
    )
    (net (code "101") (name "unconnected-(D13B-SMI_SDFS-Pad35)") (class "Default")
      (node (ref "D13") (pin "35") (pinfunction "SMI_SDFS_35") (pintype "output"))
    )
    (net (code "102") (name "unconnected-(D13B-SMI_SDO{slash}OEB-Pad33)") (class "Default")
      (node (ref "D13") (pin "33") (pinfunction "SMI_SDO/OEB_33") (pintype "bidirectional"))
    )
    (net (code "103") (name "unconnected-(D15A-CLK-Pad11)") (class "Default")
      (node (ref "D15") (pin "11") (pinfunction "CLK_11") (pintype "input"))
    )
    (net (code "104") (name "unconnected-(D15A-LD-Pad2)") (class "Default")
      (node (ref "D15") (pin "2") (pinfunction "LD_2") (pintype "output"))
    )
    (net (code "105") (name "unconnected-(D15A-OUT0-Pad42)") (class "Default")
      (node (ref "D15") (pin "42") (pinfunction "OUT0_42") (pintype "output"))
    )
    (net (code "106") (name "unconnected-(D15A-OUT1-Pad39)") (class "Default")
      (node (ref "D15") (pin "39") (pinfunction "OUT1_39") (pintype "output"))
    )
    (net (code "107") (name "unconnected-(D15A-OUT2-Pad19)") (class "Default")
      (node (ref "D15") (pin "19") (pinfunction "OUT2_19") (pintype "output"))
    )
    (net (code "108") (name "unconnected-(D15A-OUT3-Pad22)") (class "Default")
      (node (ref "D15") (pin "22") (pinfunction "OUT3_22") (pintype "output"))
    )
    (net (code "109") (name "unconnected-(D15A-OUT5(OUT5A)-Pad33)") (class "Default")
      (node (ref "D15") (pin "33") (pinfunction "OUT5(OUT5A)_33") (pintype "output"))
    )
    (net (code "110") (name "unconnected-(D15A-OUT6(OUT6A)-Pad26)") (class "Default")
      (node (ref "D15") (pin "26") (pinfunction "OUT6(OUT6A)_26") (pintype "output"))
    )
    (net (code "111") (name "unconnected-(D15A-OUT7(OUT7A)-Pad28)") (class "Default")
      (node (ref "D15") (pin "28") (pinfunction "OUT7(OUT7A)_28") (pintype "output"))
    )
    (net (code "112") (name "unconnected-(D15A-~{OUT0}-Pad41)") (class "Default")
      (node (ref "D15") (pin "41") (pinfunction "~{OUT0}_41") (pintype "output"))
    )
    (net (code "113") (name "unconnected-(D15A-~{OUT1}-Pad38)") (class "Default")
      (node (ref "D15") (pin "38") (pinfunction "~{OUT1}_38") (pintype "output"))
    )
    (net (code "114") (name "unconnected-(D15A-~{OUT2}-Pad20)") (class "Default")
      (node (ref "D15") (pin "20") (pinfunction "~{OUT2}_20") (pintype "output"))
    )
    (net (code "115") (name "unconnected-(D15A-~{OUT3}-Pad23)") (class "Default")
      (node (ref "D15") (pin "23") (pinfunction "~{OUT3}_23") (pintype "output"))
    )
    (net (code "116") (name "unconnected-(D15A-~{OUT5}(OUT5B)-Pad32)") (class "Default")
      (node (ref "D15") (pin "32") (pinfunction "~{OUT5}(OUT5B)_32") (pintype "output"))
    )
    (net (code "117") (name "unconnected-(D15A-~{OUT6}(OUT6B)-Pad27)") (class "Default")
      (node (ref "D15") (pin "27") (pinfunction "~{OUT6}(OUT6B)_27") (pintype "output"))
    )
    (net (code "118") (name "unconnected-(D15A-~{OUT7}(OUT7B)-Pad29)") (class "Default")
      (node (ref "D15") (pin "29") (pinfunction "~{OUT7}(OUT7B)_29") (pintype "output"))
    )
    (net (code "119") (name "unconnected-(D15A-~{PD}-Pad18)") (class "Default")
      (node (ref "D15") (pin "18") (pinfunction "~{PD}_18") (pintype "input"))
    )
    (net (code "120") (name "unconnected-(D15A-~{RESET}-Pad17)") (class "Default")
      (node (ref "D15") (pin "17") (pinfunction "~{RESET}_17") (pintype "input"))
    )
    (net (code "121") (name "unconnected-(D15A-~{SYNC}-Pad7)") (class "Default")
      (node (ref "D15") (pin "7") (pinfunction "~{SYNC}_7") (pintype "input"))
    )
    (net (code "122") (name "unconnected-(T1-Pad5)") (class "Default")
      (node (ref "T1") (pin "5") (pinfunction "5_5") (pintype "passive"))
    )
    (net (code "123") (name "unconnected-(T2-Pad5)") (class "Default")
      (node (ref "T2") (pin "5") (pinfunction "5_5") (pintype "passive"))
    )
  )
)
